# 4G_Module.net
KiCad netlist of a schematic drawn in Altium Designer
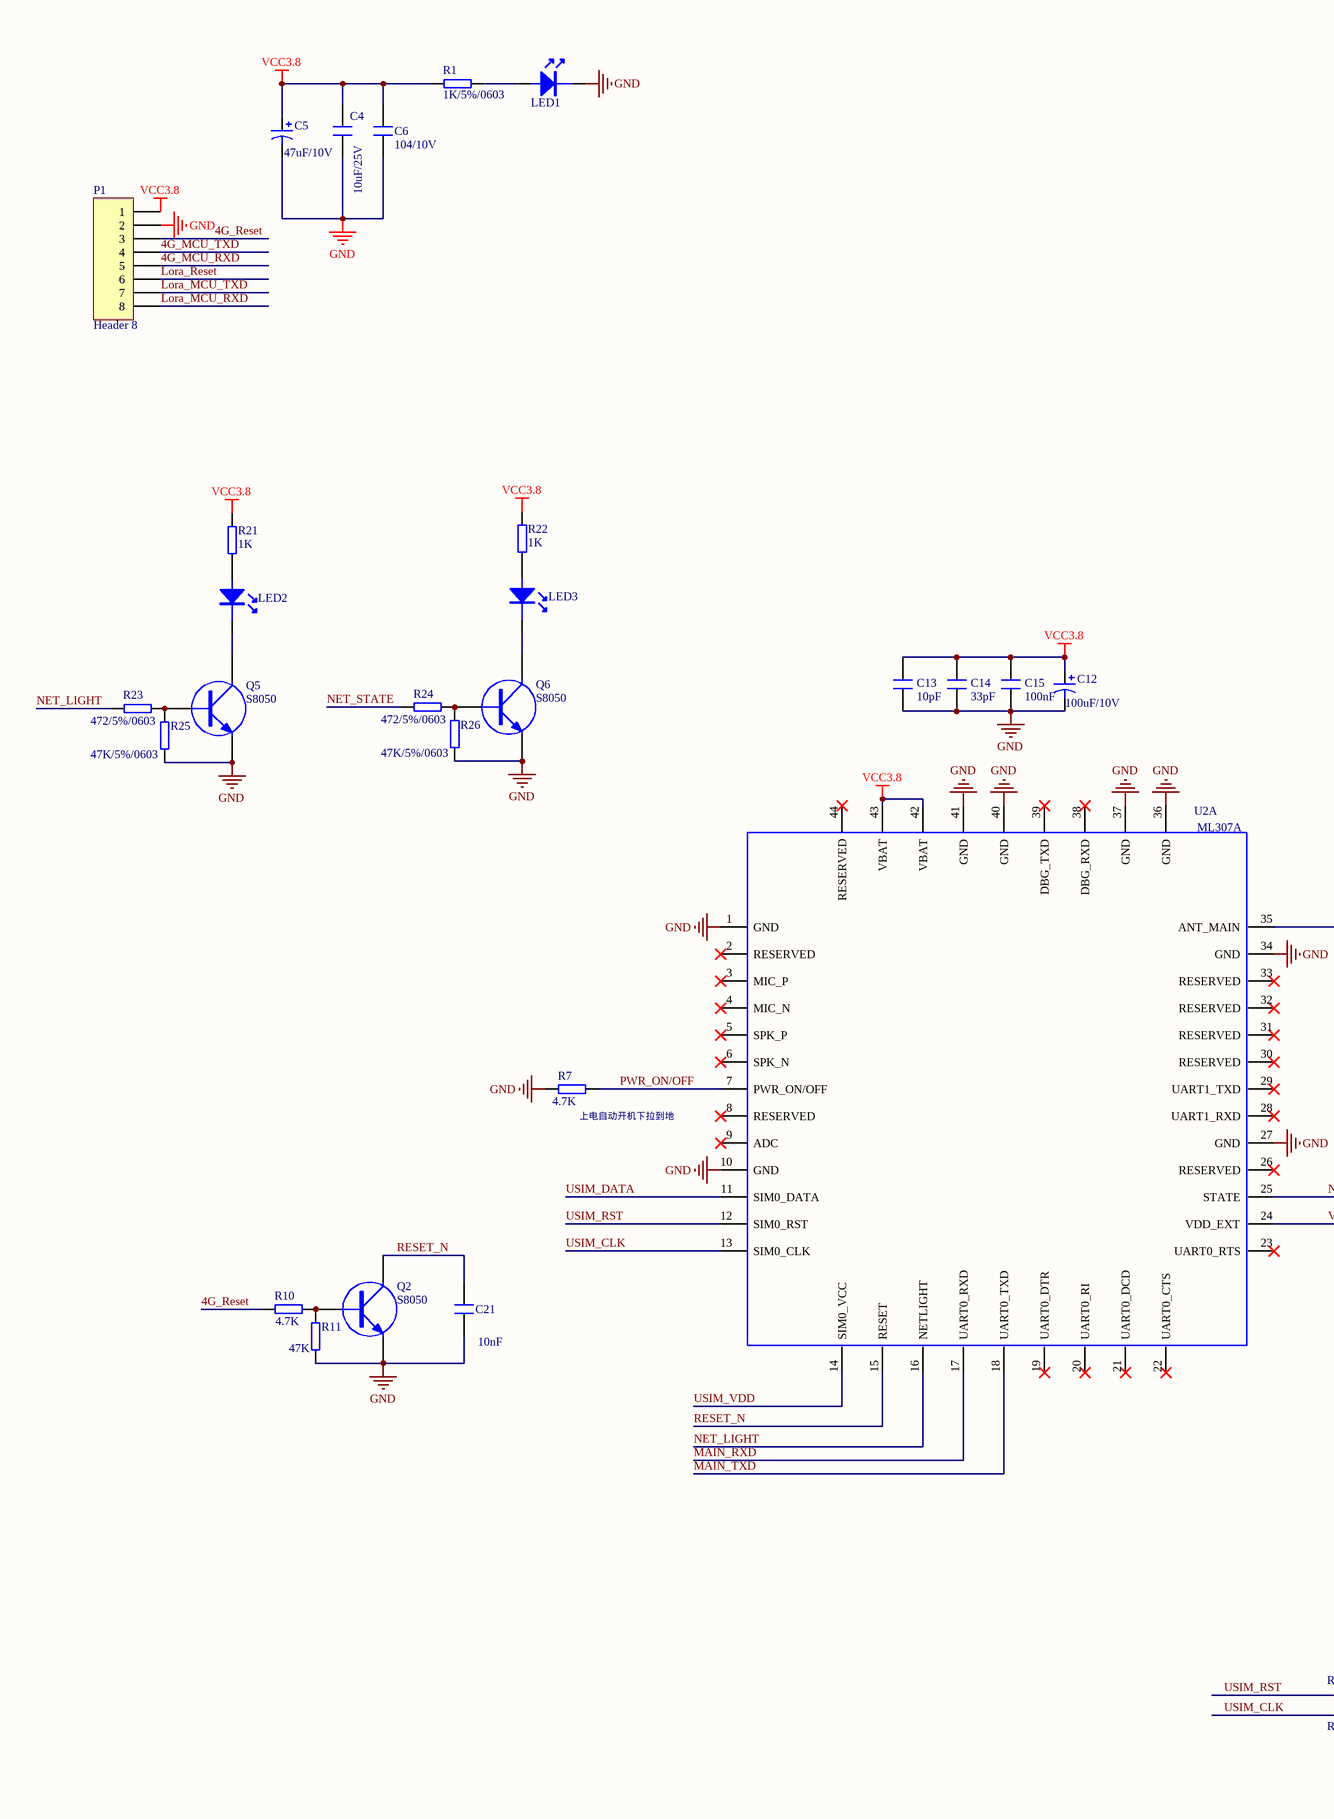
[diagram p0: 4G_Module.SchDoc, left]
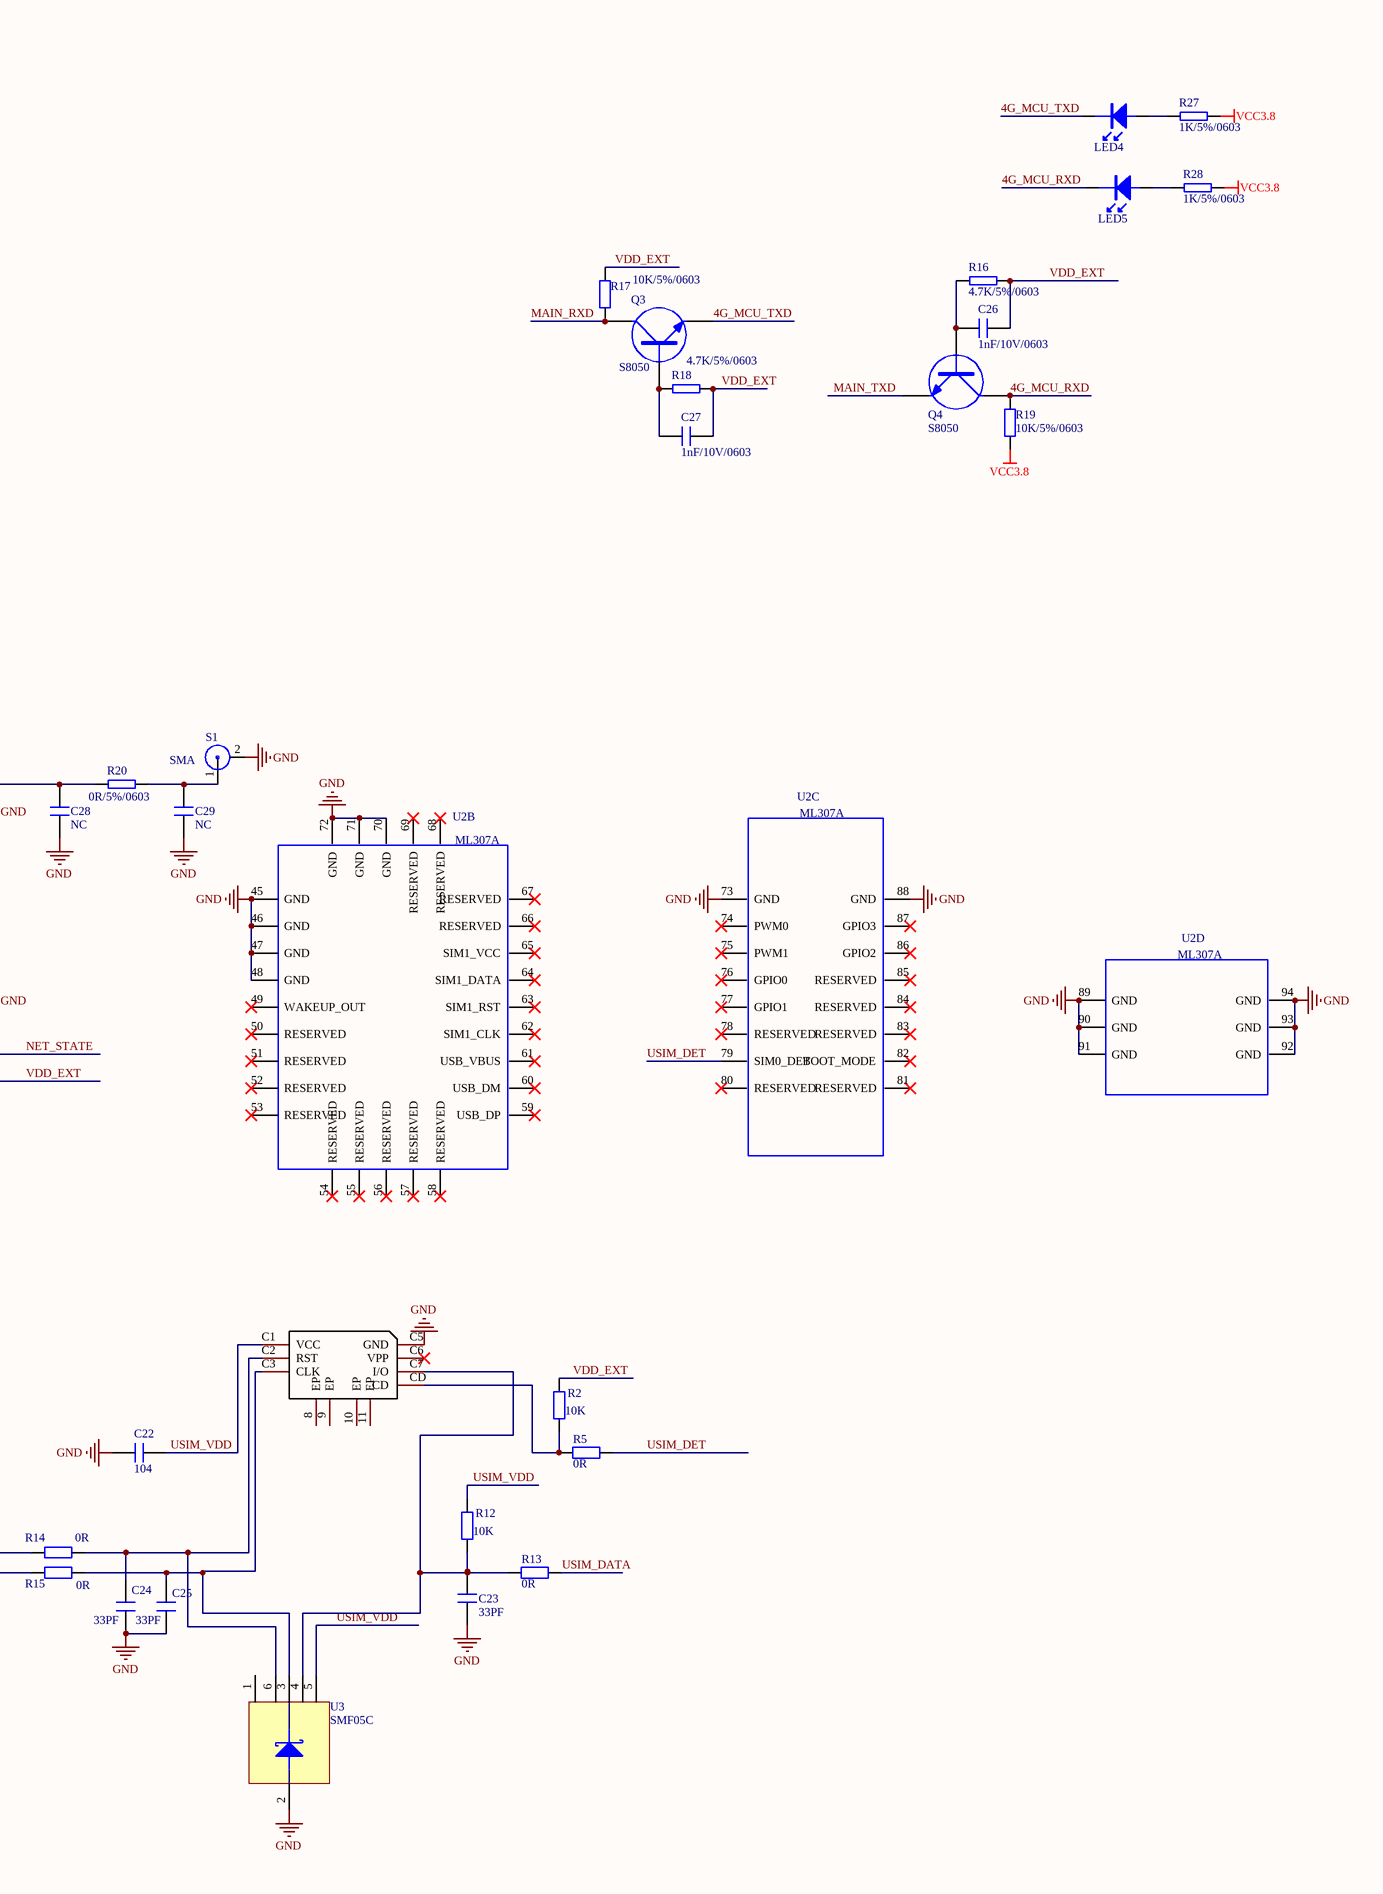
[diagram p1: 4G_Module.SchDoc, right]

(export (version "E")
  (design (tool "Eeschema 10.0.6"))
  (components
    (comp (ref "C4") (value "10uF/25V") (footprint "0603R") (libsource (lib "ES_Schematic") (part "CAP")))
    (comp (ref "C5")
      (value "47uF/10V")
      (footprint "0805R")
      (description "Polarized Capacitor (Radial)")
      (fields (field (name "PUBLISHER") "Altium Limited"))
      (libsource (lib "Miscellaneous Devices") (part "Cap Pol1"))
    )
    (comp (ref "C6") (value "104/10V") (footprint "0603R") (libsource (lib "ES_Schematic") (part "CAP_1")))
    (comp (ref "C12")
      (value "100uF/10V")
      (footprint "C1210")
      (description "Polarized Capacitor (Radial)")
      (fields (field (name "PUBLISHER") "Altium Limited"))
      (libsource (lib "Miscellaneous Devices") (part "Cap Pol1"))
    )
    (comp (ref "C13") (value "10pF") (footprint "0603R") (libsource (lib "ES_Schematic") (part "CAP_1")))
    (comp (ref "C14") (value "33pF") (footprint "0603R") (libsource (lib "ES_Schematic") (part "CAP_1")))
    (comp (ref "C15") (value "100nF") (footprint "0603R") (libsource (lib "ES_Schematic") (part "CAP_1")))
    (comp (ref "C21") (value "10nF") (footprint "0603R") (libsource (lib "ES_Schematic") (part "CAP_1")))
    (comp (ref "C22") (value "104") (footprint "0603R") (libsource (lib "ES_Schematic") (part "CAP")))
    (comp (ref "C23") (value "33PF") (footprint "0603R") (libsource (lib "ES_Schematic") (part "CAP")))
    (comp (ref "C24") (value "33PF") (footprint "0603R") (libsource (lib "ES_Schematic") (part "CAP")))
    (comp (ref "C25") (value "33PF") (footprint "0603R") (libsource (lib "ES_Schematic") (part "CAP")))
    (comp (ref "C26")
      (value "1nF/10V/0603")
      (footprint "0603R")
      (libsource (lib "ES_Schematic") (part "CAP"))
    )
    (comp (ref "C27")
      (value "1nF/10V/0603")
      (footprint "0603R")
      (libsource (lib "ES_Schematic") (part "CAP"))
    )
    (comp (ref "C28") (value "NC") (footprint "0603R") (libsource (lib "ES_Schematic") (part "CAP")))
    (comp (ref "C29") (value "NC") (footprint "0603R") (libsource (lib "ES_Schematic") (part "CAP")))
    (comp (ref "CARD1")
      (value "SMN-303")
      (footprint "Nano-SIM")
      (fields (field (name "MANUFACTURER") "XUNPU(讯普)"))
      (libsource (lib "altium-import") (part "root_0_SMN-303_"))
    )
    (comp (ref "LED1") (value "LED") (footprint "0603LED") (libsource (lib "ES_Schematic") (part "LED")))
    (comp (ref "LED2") (value "LED") (footprint "0603LED") (libsource (lib "ES_Schematic") (part "LED")))
    (comp (ref "LED3") (value "LED") (footprint "0603LED") (libsource (lib "ES_Schematic") (part "LED")))
    (comp (ref "LED4") (value "LED") (footprint "0603LED") (libsource (lib "ES_Schematic") (part "LED")))
    (comp (ref "LED5") (value "LED") (footprint "0603LED") (libsource (lib "ES_Schematic") (part "LED")))
    (comp (ref "P1")
      (value "Header 8")
      (footprint "HDR1X8")
      (description "Header, 8-Pin")
      (fields (field (name "PUBLISHER") "Altium Limited"))
      (libsource (lib "Miscellaneous Connectors") (part "Header 8"))
    )
    (comp (ref "Q2") (value "S8050") (footprint "SOT-23") (libsource (lib "ES_Schematic") (part "NPN")))
    (comp (ref "Q3") (value "S8050") (footprint "SOT-23") (libsource (lib "ES_Schematic") (part "NPN")))
    (comp (ref "Q4") (value "S8050") (footprint "SOT-23") (libsource (lib "ES_Schematic") (part "NPN")))
    (comp (ref "Q5") (value "S8050") (footprint "SOT-23") (libsource (lib "ES_Schematic") (part "NPN")))
    (comp (ref "Q6") (value "S8050") (footprint "SOT-23") (libsource (lib "ES_Schematic") (part "NPN")))
    (comp (ref "R1") (value "1K/5%/0603") (footprint "0603R") (libsource (lib "ES_Schematic") (part "RES")))
    (comp (ref "R2")
      (value "10K")
      (footprint "0603R")
      (description "Resistor")
      (fields (field (name "PUBLISHER") "Altium Limited"))
      (libsource (lib "Miscellaneous Devices") (part "Res2"))
    )
    (comp (ref "R5")
      (value "0R")
      (footprint "0603R")
      (description "Resistor")
      (fields (field (name "PUBLISHER") "Altium Limited"))
      (libsource (lib "") (part "Res2_1"))
    )
    (comp (ref "R7") (value "4.7K") (footprint "0603R") (libsource (lib "ES_Schematic") (part "RES")))
    (comp (ref "R10") (value "4.7K") (footprint "0603R") (libsource (lib "ES_Schematic") (part "RES")))
    (comp (ref "R11") (value "47K") (footprint "0603R") (libsource (lib "ES_Schematic") (part "RES")))
    (comp (ref "R12")
      (value "10K")
      (footprint "0603R")
      (description "Resistor")
      (fields (field (name "PUBLISHER") "Altium Limited"))
      (libsource (lib "Miscellaneous Devices") (part "Res2"))
    )
    (comp (ref "R13")
      (value "0R")
      (footprint "0603R")
      (description "Resistor")
      (fields (field (name "PUBLISHER") "Altium Limited"))
      (libsource (lib "") (part "Res2_1"))
    )
    (comp (ref "R14")
      (value "0R")
      (footprint "0603R")
      (description "Resistor")
      (fields (field (name "PUBLISHER") "Altium Limited"))
      (libsource (lib "") (part "Res2_1"))
    )
    (comp (ref "R15")
      (value "0R")
      (footprint "0603R")
      (description "Resistor")
      (fields (field (name "PUBLISHER") "Altium Limited"))
      (libsource (lib "") (part "Res2_1"))
    )
    (comp (ref "R16")
      (value "4.7K/5%/0603")
      (footprint "0603R")
      (libsource (lib "ES_Schematic") (part "RES"))
    )
    (comp (ref "R17")
      (value "10K/5%/0603")
      (footprint "0603R")
      (description "Resistor")
      (fields (field (name "PUBLISHER") "Altium Limited"))
      (libsource (lib "Miscellaneous Devices") (part "Res2"))
    )
    (comp (ref "R18")
      (value "4.7K/5%/0603")
      (footprint "0603R")
      (libsource (lib "ES_Schematic") (part "RES"))
    )
    (comp (ref "R19")
      (value "10K/5%/0603")
      (footprint "0603R")
      (description "Resistor")
      (fields (field (name "PUBLISHER") "Altium Limited"))
      (libsource (lib "Miscellaneous Devices") (part "Res2"))
    )
    (comp (ref "R20") (value "0R/5%/0603") (footprint "0603R") (libsource (lib "ES_Schematic") (part "RES")))
    (comp (ref "R21") (value "1K") (footprint "0603R") (libsource (lib "ES_Schematic") (part "RES")))
    (comp (ref "R22") (value "1K") (footprint "0603R") (libsource (lib "ES_Schematic") (part "RES")))
    (comp (ref "R23") (value "472/5%/0603") (footprint "0603R") (libsource (lib "ES_Schematic") (part "RES")))
    (comp (ref "R24") (value "472/5%/0603") (footprint "0603R") (libsource (lib "ES_Schematic") (part "RES")))
    (comp (ref "R25") (value "47K/5%/0603") (footprint "0603R") (libsource (lib "ES_Schematic") (part "RES")))
    (comp (ref "R26") (value "47K/5%/0603") (footprint "0603R") (libsource (lib "ES_Schematic") (part "RES")))
    (comp (ref "R27") (value "1K/5%/0603") (footprint "0603R") (libsource (lib "ES_Schematic") (part "RES")))
    (comp (ref "R28") (value "1K/5%/0603") (footprint "0603R") (libsource (lib "ES_Schematic") (part "RES")))
    (comp (ref "S1") (value "SMA") (footprint "RF1-00283天线座") (libsource (lib "ES_Schematic") (part "SMA")))
    (comp (ref "U2") (value "ML307A") (footprint "ML307A") (libsource (lib "") (part "ML307A_3")))
    (comp (ref "U3") (value "SMF05C") (footprint "SC70-6L") (libsource (lib "ES_Schematic") (part "SMF05C")))
  )
  (nets
    (net (code "1") (name "/4G_MCU_RXD") (class "Default")
      (node (ref "LED5") (pin "2") (pinfunction "2_2") (pintype "passive"))
      (node (ref "P1") (pin "5") (pinfunction "5_5") (pintype "passive"))
      (node (ref "Q4") (pin "3") (pinfunction "C_3") (pintype "passive"))
      (node (ref "R19") (pin "1") (pinfunction "1_1") (pintype "passive"))
    )
    (net (code "2") (name "/4G_MCU_TXD") (class "Default")
      (node (ref "LED4") (pin "2") (pinfunction "2_2") (pintype "passive"))
      (node (ref "P1") (pin "4") (pinfunction "4_4") (pintype "passive"))
      (node (ref "Q3") (pin "2") (pinfunction "E_2") (pintype "passive"))
    )
    (net (code "3") (name "/4G_Reset") (class "Default")
      (node (ref "P1") (pin "3") (pinfunction "3_3") (pintype "passive"))
      (node (ref "R10") (pin "1") (pinfunction "1_1") (pintype "passive"))
    )
    (net (code "4") (name "/Lora_MCU_RXD") (class "Default")
      (node (ref "P1") (pin "8") (pinfunction "8_8") (pintype "passive"))
    )
    (net (code "5") (name "/Lora_MCU_TXD") (class "Default")
      (node (ref "P1") (pin "7") (pinfunction "7_7") (pintype "passive"))
    )
    (net (code "6") (name "/Lora_Reset") (class "Default")
      (node (ref "P1") (pin "6") (pinfunction "6_6") (pintype "passive"))
    )
    (net (code "7") (name "/MAIN_RXD") (class "Default")
      (node (ref "Q3") (pin "3") (pinfunction "C_3") (pintype "passive"))
      (node (ref "R17") (pin "2") (pinfunction "2_2") (pintype "passive"))
      (node (ref "U2") (pin "17") (pinfunction "UART0_RXD_17") (pintype "passive"))
    )
    (net (code "8") (name "/MAIN_TXD") (class "Default")
      (node (ref "Q4") (pin "2") (pinfunction "E_2") (pintype "passive"))
      (node (ref "U2") (pin "18") (pinfunction "UART0_TXD_18") (pintype "passive"))
    )
    (net (code "9") (name "/NET_LIGHT") (class "Default")
      (node (ref "R23") (pin "1") (pinfunction "1_1") (pintype "passive"))
      (node (ref "U2") (pin "16") (pinfunction "NETLIGHT_16") (pintype "passive"))
    )
    (net (code "10") (name "/NET_STATE") (class "Default")
      (node (ref "R24") (pin "1") (pinfunction "1_1") (pintype "passive"))
      (node (ref "U2") (pin "25") (pinfunction "STATE_25") (pintype "passive"))
    )
    (net (code "11") (name "/PWR_ON{slash}OFF") (class "Default")
      (node (ref "R7") (pin "1") (pinfunction "1_1") (pintype "passive"))
      (node (ref "U2") (pin "7") (pinfunction "PWR_ON/OFF_7") (pintype "passive"))
    )
    (net (code "12") (name "/RESET_N") (class "Default")
      (node (ref "C21") (pin "2") (pinfunction "2_2") (pintype "passive"))
      (node (ref "Q2") (pin "3") (pinfunction "C_3") (pintype "passive"))
      (node (ref "U2") (pin "15") (pinfunction "RESET_15") (pintype "passive"))
    )
    (net (code "13") (name "/USIM_CLK") (class "Default")
      (node (ref "R15") (pin "2") (pinfunction "2_2") (pintype "passive"))
      (node (ref "U2") (pin "13") (pinfunction "SIM0_CLK_13") (pintype "passive"))
    )
    (net (code "14") (name "/USIM_DATA") (class "Default")
      (node (ref "R13") (pin "1") (pinfunction "1_1") (pintype "passive"))
      (node (ref "U2") (pin "11") (pinfunction "SIM0_DATA_11") (pintype "passive"))
    )
    (net (code "15") (name "/USIM_DET") (class "Default")
      (node (ref "R5") (pin "1") (pinfunction "1_1") (pintype "passive"))
      (node (ref "U2") (pin "79") (pinfunction "SIM0_DET_79") (pintype "passive"))
    )
    (net (code "16") (name "/USIM_RST") (class "Default")
      (node (ref "R14") (pin "2") (pinfunction "2_2") (pintype "passive"))
      (node (ref "U2") (pin "12") (pinfunction "SIM0_RST_12") (pintype "passive"))
    )
    (net (code "17") (name "/USIM_VDD") (class "Default")
      (node (ref "C22") (pin "2") (pinfunction "2_2") (pintype "passive"))
      (node (ref "CARD1") (pin "C1") (pinfunction "VCC_C1") (pintype "passive"))
      (node (ref "R12") (pin "1") (pinfunction "1_1") (pintype "passive"))
      (node (ref "U2") (pin "14") (pinfunction "SIM0_VCC_14") (pintype "passive"))
      (node (ref "U3") (pin "5") (pintype "passive"))
    )
    (net (code "18") (name "/VDD_EXT") (class "Default")
      (node (ref "C26") (pin "2") (pinfunction "2_2") (pintype "passive"))
      (node (ref "C27") (pin "2") (pinfunction "2_2") (pintype "passive"))
      (node (ref "R16") (pin "2") (pinfunction "2_2") (pintype "passive"))
      (node (ref "R17") (pin "1") (pinfunction "1_1") (pintype "passive"))
      (node (ref "R18") (pin "2") (pinfunction "2_2") (pintype "passive"))
      (node (ref "R2") (pin "1") (pinfunction "1_1") (pintype "passive"))
      (node (ref "U2") (pin "24") (pinfunction "VDD_EXT_24") (pintype "passive"))
    )
    (net (code "19") (name "GND") (class "Default")
      (node (ref "C12") (pin "2") (pinfunction "2_2") (pintype "passive"))
      (node (ref "C13") (pin "2") (pinfunction "2_2") (pintype "passive"))
      (node (ref "C14") (pin "2") (pinfunction "2_2") (pintype "passive"))
      (node (ref "C15") (pin "2") (pinfunction "2_2") (pintype "passive"))
      (node (ref "C21") (pin "1") (pinfunction "1_1") (pintype "passive"))
      (node (ref "C22") (pin "1") (pinfunction "1_1") (pintype "passive"))
      (node (ref "C23") (pin "1") (pinfunction "1_1") (pintype "passive"))
      (node (ref "C24") (pin "2") (pinfunction "2_2") (pintype "passive"))
      (node (ref "C25") (pin "2") (pinfunction "2_2") (pintype "passive"))
      (node (ref "C28") (pin "1") (pinfunction "1_1") (pintype "passive"))
      (node (ref "C29") (pin "1") (pinfunction "1_1") (pintype "passive"))
      (node (ref "C4") (pin "1") (pinfunction "1_1") (pintype "passive"))
      (node (ref "C5") (pin "2") (pinfunction "2_2") (pintype "passive"))
      (node (ref "C6") (pin "1") (pinfunction "1_1") (pintype "passive"))
      (node (ref "CARD1") (pin "C5") (pinfunction "GND_C5") (pintype "passive"))
      (node (ref "LED1") (pin "2") (pinfunction "2_2") (pintype "passive"))
      (node (ref "P1") (pin "2") (pinfunction "2_2") (pintype "passive"))
      (node (ref "Q2") (pin "2") (pinfunction "E_2") (pintype "passive"))
      (node (ref "Q5") (pin "2") (pinfunction "E_2") (pintype "passive"))
      (node (ref "Q6") (pin "2") (pinfunction "E_2") (pintype "passive"))
      (node (ref "R11") (pin "2") (pinfunction "2_2") (pintype "passive"))
      (node (ref "R25") (pin "2") (pinfunction "2_2") (pintype "passive"))
      (node (ref "R26") (pin "2") (pinfunction "2_2") (pintype "passive"))
      (node (ref "R7") (pin "2") (pinfunction "2_2") (pintype "passive"))
      (node (ref "S1") (pin "2") (pinfunction "2_2") (pintype "passive"))
      (node (ref "U2") (pin "1") (pinfunction "GND_1") (pintype "passive"))
      (node (ref "U2") (pin "10") (pinfunction "GND_10") (pintype "passive"))
      (node (ref "U2") (pin "27") (pinfunction "GND_27") (pintype "passive"))
      (node (ref "U2") (pin "34") (pinfunction "GND_34") (pintype "passive"))
      (node (ref "U2") (pin "36") (pinfunction "GND_36") (pintype "passive"))
      (node (ref "U2") (pin "37") (pinfunction "GND_37") (pintype "passive"))
      (node (ref "U2") (pin "40") (pinfunction "GND_40") (pintype "passive"))
      (node (ref "U2") (pin "41") (pinfunction "GND_41") (pintype "passive"))
      (node (ref "U2") (pin "45") (pinfunction "GND_45") (pintype "passive"))
      (node (ref "U2") (pin "46") (pinfunction "GND_46") (pintype "passive"))
      (node (ref "U2") (pin "47") (pinfunction "GND_47") (pintype "passive"))
      (node (ref "U2") (pin "48") (pinfunction "GND_48") (pintype "passive"))
      (node (ref "U2") (pin "70") (pinfunction "GND_70") (pintype "passive"))
      (node (ref "U2") (pin "71") (pinfunction "GND_71") (pintype "passive"))
      (node (ref "U2") (pin "72") (pinfunction "GND_72") (pintype "passive"))
      (node (ref "U2") (pin "73") (pinfunction "GND_73") (pintype "passive"))
      (node (ref "U2") (pin "88") (pinfunction "GND_88") (pintype "passive"))
      (node (ref "U2") (pin "89") (pinfunction "GND_89") (pintype "passive"))
      (node (ref "U2") (pin "90") (pinfunction "GND_90") (pintype "passive"))
      (node (ref "U2") (pin "91") (pinfunction "GND_91") (pintype "passive"))
      (node (ref "U2") (pin "92") (pinfunction "GND_92") (pintype "passive"))
      (node (ref "U2") (pin "93") (pinfunction "GND_93") (pintype "passive"))
      (node (ref "U2") (pin "94") (pinfunction "GND_94") (pintype "passive"))
      (node (ref "U3") (pin "2") (pintype "passive"))
    )
    (net (code "20") (name "Net-(C29-Pad2)") (class "Default")
      (node (ref "C29") (pin "2") (pinfunction "2_2") (pintype "passive"))
      (node (ref "R20") (pin "2") (pinfunction "2_2") (pintype "passive"))
      (node (ref "S1") (pin "1") (pinfunction "1_1") (pintype "passive"))
    )
    (net (code "21") (name "Net-(CARD1-CLK)") (class "Default")
      (node (ref "C25") (pin "1") (pinfunction "1_1") (pintype "passive"))
      (node (ref "CARD1") (pin "C3") (pinfunction "CLK_C3") (pintype "passive"))
      (node (ref "R15") (pin "1") (pinfunction "1_1") (pintype "passive"))
      (node (ref "U3") (pin "3") (pintype "passive"))
    )
    (net (code "22") (name "Net-(CARD1-I{slash}O)") (class "Default")
      (node (ref "C23") (pin "2") (pinfunction "2_2") (pintype "passive"))
      (node (ref "CARD1") (pin "C7") (pinfunction "I/O_C7") (pintype "passive"))
      (node (ref "R12") (pin "2") (pinfunction "2_2") (pintype "passive"))
      (node (ref "R13") (pin "2") (pinfunction "2_2") (pintype "passive"))
      (node (ref "U3") (pin "4") (pintype "passive"))
    )
    (net (code "23") (name "Net-(CARD1-PadCD)") (class "Default")
      (node (ref "CARD1") (pin "CD") (pinfunction "CD_CD") (pintype "passive"))
      (node (ref "R2") (pin "2") (pinfunction "2_2") (pintype "passive"))
      (node (ref "R5") (pin "2") (pinfunction "2_2") (pintype "passive"))
    )
    (net (code "24") (name "Net-(CARD1-RST)") (class "Default")
      (node (ref "C24") (pin "1") (pinfunction "1_1") (pintype "passive"))
      (node (ref "CARD1") (pin "C2") (pinfunction "RST_C2") (pintype "passive"))
      (node (ref "R14") (pin "1") (pinfunction "1_1") (pintype "passive"))
      (node (ref "U3") (pin "6") (pintype "passive"))
    )
    (net (code "25") (name "Net-(LED1-Pad1)") (class "Default")
      (node (ref "LED1") (pin "1") (pinfunction "1_1") (pintype "passive"))
      (node (ref "R1") (pin "2") (pinfunction "2_2") (pintype "passive"))
    )
    (net (code "26") (name "Net-(LED2-Pad1)") (class "Default")
      (node (ref "LED2") (pin "1") (pinfunction "1_1") (pintype "passive"))
      (node (ref "R21") (pin "1") (pinfunction "1_1") (pintype "passive"))
    )
    (net (code "27") (name "Net-(LED3-Pad1)") (class "Default")
      (node (ref "LED3") (pin "1") (pinfunction "1_1") (pintype "passive"))
      (node (ref "R22") (pin "1") (pinfunction "1_1") (pintype "passive"))
    )
    (net (code "28") (name "Net-(LED4-Pad1)") (class "Default")
      (node (ref "LED4") (pin "1") (pinfunction "1_1") (pintype "passive"))
      (node (ref "R27") (pin "2") (pinfunction "2_2") (pintype "passive"))
    )
    (net (code "29") (name "Net-(LED5-Pad1)") (class "Default")
      (node (ref "LED5") (pin "1") (pinfunction "1_1") (pintype "passive"))
      (node (ref "R28") (pin "2") (pinfunction "2_2") (pintype "passive"))
    )
    (net (code "30") (name "Net-(Q2-B)") (class "Default")
      (node (ref "Q2") (pin "1") (pinfunction "B_1") (pintype "passive"))
      (node (ref "R10") (pin "2") (pinfunction "2_2") (pintype "passive"))
      (node (ref "R11") (pin "1") (pinfunction "1_1") (pintype "passive"))
    )
    (net (code "31") (name "Net-(Q3-B)") (class "Default")
      (node (ref "C27") (pin "1") (pinfunction "1_1") (pintype "passive"))
      (node (ref "Q3") (pin "1") (pinfunction "B_1") (pintype "passive"))
      (node (ref "R18") (pin "1") (pinfunction "1_1") (pintype "passive"))
    )
    (net (code "32") (name "Net-(Q4-B)") (class "Default")
      (node (ref "C26") (pin "1") (pinfunction "1_1") (pintype "passive"))
      (node (ref "Q4") (pin "1") (pinfunction "B_1") (pintype "passive"))
      (node (ref "R16") (pin "1") (pinfunction "1_1") (pintype "passive"))
    )
    (net (code "33") (name "Net-(Q5-B)") (class "Default")
      (node (ref "Q5") (pin "1") (pinfunction "B_1") (pintype "passive"))
      (node (ref "R23") (pin "2") (pinfunction "2_2") (pintype "passive"))
      (node (ref "R25") (pin "1") (pinfunction "1_1") (pintype "passive"))
    )
    (net (code "34") (name "Net-(Q5-C)") (class "Default")
      (node (ref "LED2") (pin "2") (pinfunction "2_2") (pintype "passive"))
      (node (ref "Q5") (pin "3") (pinfunction "C_3") (pintype "passive"))
    )
    (net (code "35") (name "Net-(Q6-B)") (class "Default")
      (node (ref "Q6") (pin "1") (pinfunction "B_1") (pintype "passive"))
      (node (ref "R24") (pin "2") (pinfunction "2_2") (pintype "passive"))
      (node (ref "R26") (pin "1") (pinfunction "1_1") (pintype "passive"))
    )
    (net (code "36") (name "Net-(Q6-C)") (class "Default")
      (node (ref "LED3") (pin "2") (pinfunction "2_2") (pintype "passive"))
      (node (ref "Q6") (pin "3") (pinfunction "C_3") (pintype "passive"))
    )
    (net (code "37") (name "Net-(U2A-ANT_MAIN)") (class "Default")
      (node (ref "C28") (pin "2") (pinfunction "2_2") (pintype "passive"))
      (node (ref "R20") (pin "1") (pinfunction "1_1") (pintype "passive"))
      (node (ref "U2") (pin "35") (pinfunction "ANT_MAIN_35") (pintype "passive"))
    )
    (net (code "38") (name "VCC3.8") (class "Default")
      (node (ref "C12") (pin "1") (pinfunction "1_1") (pintype "passive"))
      (node (ref "C13") (pin "1") (pinfunction "1_1") (pintype "passive"))
      (node (ref "C14") (pin "1") (pinfunction "1_1") (pintype "passive"))
      (node (ref "C15") (pin "1") (pinfunction "1_1") (pintype "passive"))
      (node (ref "C4") (pin "2") (pinfunction "2_2") (pintype "passive"))
      (node (ref "C5") (pin "1") (pinfunction "1_1") (pintype "passive"))
      (node (ref "C6") (pin "2") (pinfunction "2_2") (pintype "passive"))
      (node (ref "P1") (pin "1") (pinfunction "1_1") (pintype "passive"))
      (node (ref "R1") (pin "1") (pinfunction "1_1") (pintype "passive"))
      (node (ref "R19") (pin "2") (pinfunction "2_2") (pintype "passive"))
      (node (ref "R21") (pin "2") (pinfunction "2_2") (pintype "passive"))
      (node (ref "R22") (pin "2") (pinfunction "2_2") (pintype "passive"))
      (node (ref "R27") (pin "1") (pinfunction "1_1") (pintype "passive"))
      (node (ref "R28") (pin "1") (pinfunction "1_1") (pintype "passive"))
      (node (ref "U2") (pin "42") (pinfunction "VBAT_42") (pintype "passive"))
      (node (ref "U2") (pin "43") (pinfunction "VBAT_43") (pintype "passive"))
    )
    (net (code "39") (name "unconnected-(CARD1-EP-Pad8)") (class "Default")
      (node (ref "CARD1") (pin "8") (pinfunction "EP_8") (pintype "passive"))
    )
    (net (code "40") (name "unconnected-(CARD1-EP-Pad9)") (class "Default")
      (node (ref "CARD1") (pin "9") (pinfunction "EP_9") (pintype "passive"))
    )
    (net (code "41") (name "unconnected-(CARD1-EP-Pad10)") (class "Default")
      (node (ref "CARD1") (pin "10") (pinfunction "EP_10") (pintype "passive"))
    )
    (net (code "42") (name "unconnected-(CARD1-EP-Pad11)") (class "Default")
      (node (ref "CARD1") (pin "11") (pinfunction "EP_11") (pintype "passive"))
    )
    (net (code "43") (name "unconnected-(CARD1-VPP-PadC6)") (class "Default")
      (node (ref "CARD1") (pin "C6") (pinfunction "VPP_C6") (pintype "passive+no_connect"))
    )
    (net (code "44") (name "unconnected-(U2A-ADC-Pad9)") (class "Default")
      (node (ref "U2") (pin "9") (pinfunction "ADC_9") (pintype "passive+no_connect"))
    )
    (net (code "45") (name "unconnected-(U2A-DBG_RXD-Pad38)") (class "Default")
      (node (ref "U2") (pin "38") (pinfunction "DBG_RXD_38") (pintype "passive+no_connect"))
    )
    (net (code "46") (name "unconnected-(U2A-DBG_TXD-Pad39)") (class "Default")
      (node (ref "U2") (pin "39") (pinfunction "DBG_TXD_39") (pintype "passive+no_connect"))
    )
    (net (code "47") (name "unconnected-(U2A-MIC_N-Pad4)") (class "Default")
      (node (ref "U2") (pin "4") (pinfunction "MIC_N_4") (pintype "passive+no_connect"))
    )
    (net (code "48") (name "unconnected-(U2A-MIC_P-Pad3)") (class "Default")
      (node (ref "U2") (pin "3") (pinfunction "MIC_P_3") (pintype "passive+no_connect"))
    )
    (net (code "49") (name "unconnected-(U2A-RESERVED-Pad2)") (class "Default")
      (node (ref "U2") (pin "2") (pinfunction "RESERVED_2") (pintype "passive+no_connect"))
    )
    (net (code "50") (name "unconnected-(U2A-RESERVED-Pad8)") (class "Default")
      (node (ref "U2") (pin "8") (pinfunction "RESERVED_8") (pintype "passive+no_connect"))
    )
    (net (code "51") (name "unconnected-(U2A-RESERVED-Pad26)") (class "Default")
      (node (ref "U2") (pin "26") (pinfunction "RESERVED_26") (pintype "passive+no_connect"))
    )
    (net (code "52") (name "unconnected-(U2A-RESERVED-Pad30)") (class "Default")
      (node (ref "U2") (pin "30") (pinfunction "RESERVED_30") (pintype "passive+no_connect"))
    )
    (net (code "53") (name "unconnected-(U2A-RESERVED-Pad31)") (class "Default")
      (node (ref "U2") (pin "31") (pinfunction "RESERVED_31") (pintype "passive+no_connect"))
    )
    (net (code "54") (name "unconnected-(U2A-RESERVED-Pad32)") (class "Default")
      (node (ref "U2") (pin "32") (pinfunction "RESERVED_32") (pintype "passive+no_connect"))
    )
    (net (code "55") (name "unconnected-(U2A-RESERVED-Pad33)") (class "Default")
      (node (ref "U2") (pin "33") (pinfunction "RESERVED_33") (pintype "passive+no_connect"))
    )
    (net (code "56") (name "unconnected-(U2A-RESERVED-Pad44)") (class "Default")
      (node (ref "U2") (pin "44") (pinfunction "RESERVED_44") (pintype "passive+no_connect"))
    )
    (net (code "57") (name "unconnected-(U2A-SPK_N-Pad6)") (class "Default")
      (node (ref "U2") (pin "6") (pinfunction "SPK_N_6") (pintype "passive+no_connect"))
    )
    (net (code "58") (name "unconnected-(U2A-SPK_P-Pad5)") (class "Default")
      (node (ref "U2") (pin "5") (pinfunction "SPK_P_5") (pintype "passive+no_connect"))
    )
    (net (code "59") (name "unconnected-(U2A-UART0_CTS-Pad22)") (class "Default")
      (node (ref "U2") (pin "22") (pinfunction "UART0_CTS_22") (pintype "passive+no_connect"))
    )
    (net (code "60") (name "unconnected-(U2A-UART0_DCD-Pad21)") (class "Default")
      (node (ref "U2") (pin "21") (pinfunction "UART0_DCD_21") (pintype "passive+no_connect"))
    )
    (net (code "61") (name "unconnected-(U2A-UART0_DTR-Pad19)") (class "Default")
      (node (ref "U2") (pin "19") (pinfunction "UART0_DTR_19") (pintype "passive+no_connect"))
    )
    (net (code "62") (name "unconnected-(U2A-UART0_RI-Pad20)") (class "Default")
      (node (ref "U2") (pin "20") (pinfunction "UART0_RI_20") (pintype "passive+no_connect"))
    )
    (net (code "63") (name "unconnected-(U2A-UART0_RTS-Pad23)") (class "Default")
      (node (ref "U2") (pin "23") (pinfunction "UART0_RTS_23") (pintype "passive+no_connect"))
    )
    (net (code "64") (name "unconnected-(U2A-UART1_RXD-Pad28)") (class "Default")
      (node (ref "U2") (pin "28") (pinfunction "UART1_RXD_28") (pintype "passive+no_connect"))
    )
    (net (code "65") (name "unconnected-(U2A-UART1_TXD-Pad29)") (class "Default")
      (node (ref "U2") (pin "29") (pinfunction "UART1_TXD_29") (pintype "passive+no_connect"))
    )
    (net (code "66") (name "unconnected-(U2B-RESERVED-Pad50)") (class "Default")
      (node (ref "U2") (pin "50") (pinfunction "RESERVED_50") (pintype "passive+no_connect"))
    )
    (net (code "67") (name "unconnected-(U2B-RESERVED-Pad51)") (class "Default")
      (node (ref "U2") (pin "51") (pinfunction "RESERVED_51") (pintype "passive+no_connect"))
    )
    (net (code "68") (name "unconnected-(U2B-RESERVED-Pad52)") (class "Default")
      (node (ref "U2") (pin "52") (pinfunction "RESERVED_52") (pintype "passive+no_connect"))
    )
    (net (code "69") (name "unconnected-(U2B-RESERVED-Pad53)") (class "Default")
      (node (ref "U2") (pin "53") (pinfunction "RESERVED_53") (pintype "passive+no_connect"))
    )
    (net (code "70") (name "unconnected-(U2B-RESERVED-Pad54)") (class "Default")
      (node (ref "U2") (pin "54") (pinfunction "RESERVED_54") (pintype "passive+no_connect"))
    )
    (net (code "71") (name "unconnected-(U2B-RESERVED-Pad55)") (class "Default")
      (node (ref "U2") (pin "55") (pinfunction "RESERVED_55") (pintype "passive+no_connect"))
    )
    (net (code "72") (name "unconnected-(U2B-RESERVED-Pad56)") (class "Default")
      (node (ref "U2") (pin "56") (pinfunction "RESERVED_56") (pintype "passive+no_connect"))
    )
    (net (code "73") (name "unconnected-(U2B-RESERVED-Pad57)") (class "Default")
      (node (ref "U2") (pin "57") (pinfunction "RESERVED_57") (pintype "passive+no_connect"))
    )
    (net (code "74") (name "unconnected-(U2B-RESERVED-Pad58)") (class "Default")
      (node (ref "U2") (pin "58") (pinfunction "RESERVED_58") (pintype "passive+no_connect"))
    )
    (net (code "75") (name "unconnected-(U2B-RESERVED-Pad66)") (class "Default")
      (node (ref "U2") (pin "66") (pinfunction "RESERVED_66") (pintype "passive+no_connect"))
    )
    (net (code "76") (name "unconnected-(U2B-RESERVED-Pad67)") (class "Default")
      (node (ref "U2") (pin "67") (pinfunction "RESERVED_67") (pintype "passive+no_connect"))
    )
    (net (code "77") (name "unconnected-(U2B-RESERVED-Pad68)") (class "Default")
      (node (ref "U2") (pin "68") (pinfunction "RESERVED_68") (pintype "passive+no_connect"))
    )
    (net (code "78") (name "unconnected-(U2B-RESERVED-Pad69)") (class "Default")
      (node (ref "U2") (pin "69") (pinfunction "RESERVED_69") (pintype "passive+no_connect"))
    )
    (net (code "79") (name "unconnected-(U2B-SIM1_CLK-Pad62)") (class "Default")
      (node (ref "U2") (pin "62") (pinfunction "SIM1_CLK_62") (pintype "passive+no_connect"))
    )
    (net (code "80") (name "unconnected-(U2B-SIM1_DATA-Pad64)") (class "Default")
      (node (ref "U2") (pin "64") (pinfunction "SIM1_DATA_64") (pintype "passive+no_connect"))
    )
    (net (code "81") (name "unconnected-(U2B-SIM1_RST-Pad63)") (class "Default")
      (node (ref "U2") (pin "63") (pinfunction "SIM1_RST_63") (pintype "passive+no_connect"))
    )
    (net (code "82") (name "unconnected-(U2B-SIM1_VCC-Pad65)") (class "Default")
      (node (ref "U2") (pin "65") (pinfunction "SIM1_VCC_65") (pintype "passive+no_connect"))
    )
    (net (code "83") (name "unconnected-(U2B-USB_DM-Pad60)") (class "Default")
      (node (ref "U2") (pin "60") (pinfunction "USB_DM_60") (pintype "passive+no_connect"))
    )
    (net (code "84") (name "unconnected-(U2B-USB_DP-Pad59)") (class "Default")
      (node (ref "U2") (pin "59") (pinfunction "USB_DP_59") (pintype "passive+no_connect"))
    )
    (net (code "85") (name "unconnected-(U2B-USB_VBUS-Pad61)") (class "Default")
      (node (ref "U2") (pin "61") (pinfunction "USB_VBUS_61") (pintype "passive+no_connect"))
    )
    (net (code "86") (name "unconnected-(U2B-WAKEUP_OUT-Pad49)") (class "Default")
      (node (ref "U2") (pin "49") (pinfunction "WAKEUP_OUT_49") (pintype "passive+no_connect"))
    )
    (net (code "87") (name "unconnected-(U2C-BOOT_MODE-Pad82)") (class "Default")
      (node (ref "U2") (pin "82") (pinfunction "BOOT_MODE_82") (pintype "passive+no_connect"))
    )
    (net (code "88") (name "unconnected-(U2C-GPIO0-Pad76)") (class "Default")
      (node (ref "U2") (pin "76") (pinfunction "GPIO0_76") (pintype "passive+no_connect"))
    )
    (net (code "89") (name "unconnected-(U2C-GPIO1-Pad77)") (class "Default")
      (node (ref "U2") (pin "77") (pinfunction "GPIO1_77") (pintype "passive+no_connect"))
    )
    (net (code "90") (name "unconnected-(U2C-GPIO2-Pad86)") (class "Default")
      (node (ref "U2") (pin "86") (pinfunction "GPIO2_86") (pintype "passive+no_connect"))
    )
    (net (code "91") (name "unconnected-(U2C-GPIO3-Pad87)") (class "Default")
      (node (ref "U2") (pin "87") (pinfunction "GPIO3_87") (pintype "passive+no_connect"))
    )
    (net (code "92") (name "unconnected-(U2C-PWM0-Pad74)") (class "Default")
      (node (ref "U2") (pin "74") (pinfunction "PWM0_74") (pintype "passive+no_connect"))
    )
    (net (code "93") (name "unconnected-(U2C-PWM1-Pad75)") (class "Default")
      (node (ref "U2") (pin "75") (pinfunction "PWM1_75") (pintype "passive+no_connect"))
    )
    (net (code "94") (name "unconnected-(U2C-RESERVED-Pad78)") (class "Default")
      (node (ref "U2") (pin "78") (pinfunction "RESERVED_78") (pintype "passive+no_connect"))
    )
    (net (code "95") (name "unconnected-(U2C-RESERVED-Pad80)") (class "Default")
      (node (ref "U2") (pin "80") (pinfunction "RESERVED_80") (pintype "passive+no_connect"))
    )
    (net (code "96") (name "unconnected-(U2C-RESERVED-Pad81)") (class "Default")
      (node (ref "U2") (pin "81") (pinfunction "RESERVED_81") (pintype "passive+no_connect"))
    )
    (net (code "97") (name "unconnected-(U2C-RESERVED-Pad83)") (class "Default")
      (node (ref "U2") (pin "83") (pinfunction "RESERVED_83") (pintype "passive+no_connect"))
    )
    (net (code "98") (name "unconnected-(U2C-RESERVED-Pad84)") (class "Default")
      (node (ref "U2") (pin "84") (pinfunction "RESERVED_84") (pintype "passive+no_connect"))
    )
    (net (code "99") (name "unconnected-(U2C-RESERVED-Pad85)") (class "Default")
      (node (ref "U2") (pin "85") (pinfunction "RESERVED_85") (pintype "passive+no_connect"))
    )
    (net (code "100") (name "unconnected-(U3-Pad1)") (class "Default")
      (node (ref "U3") (pin "1") (pintype "passive"))
    )
  )
)
